# SCH_heterodyne.net
KiCad netlist of a schematic drawn in EasyEDA
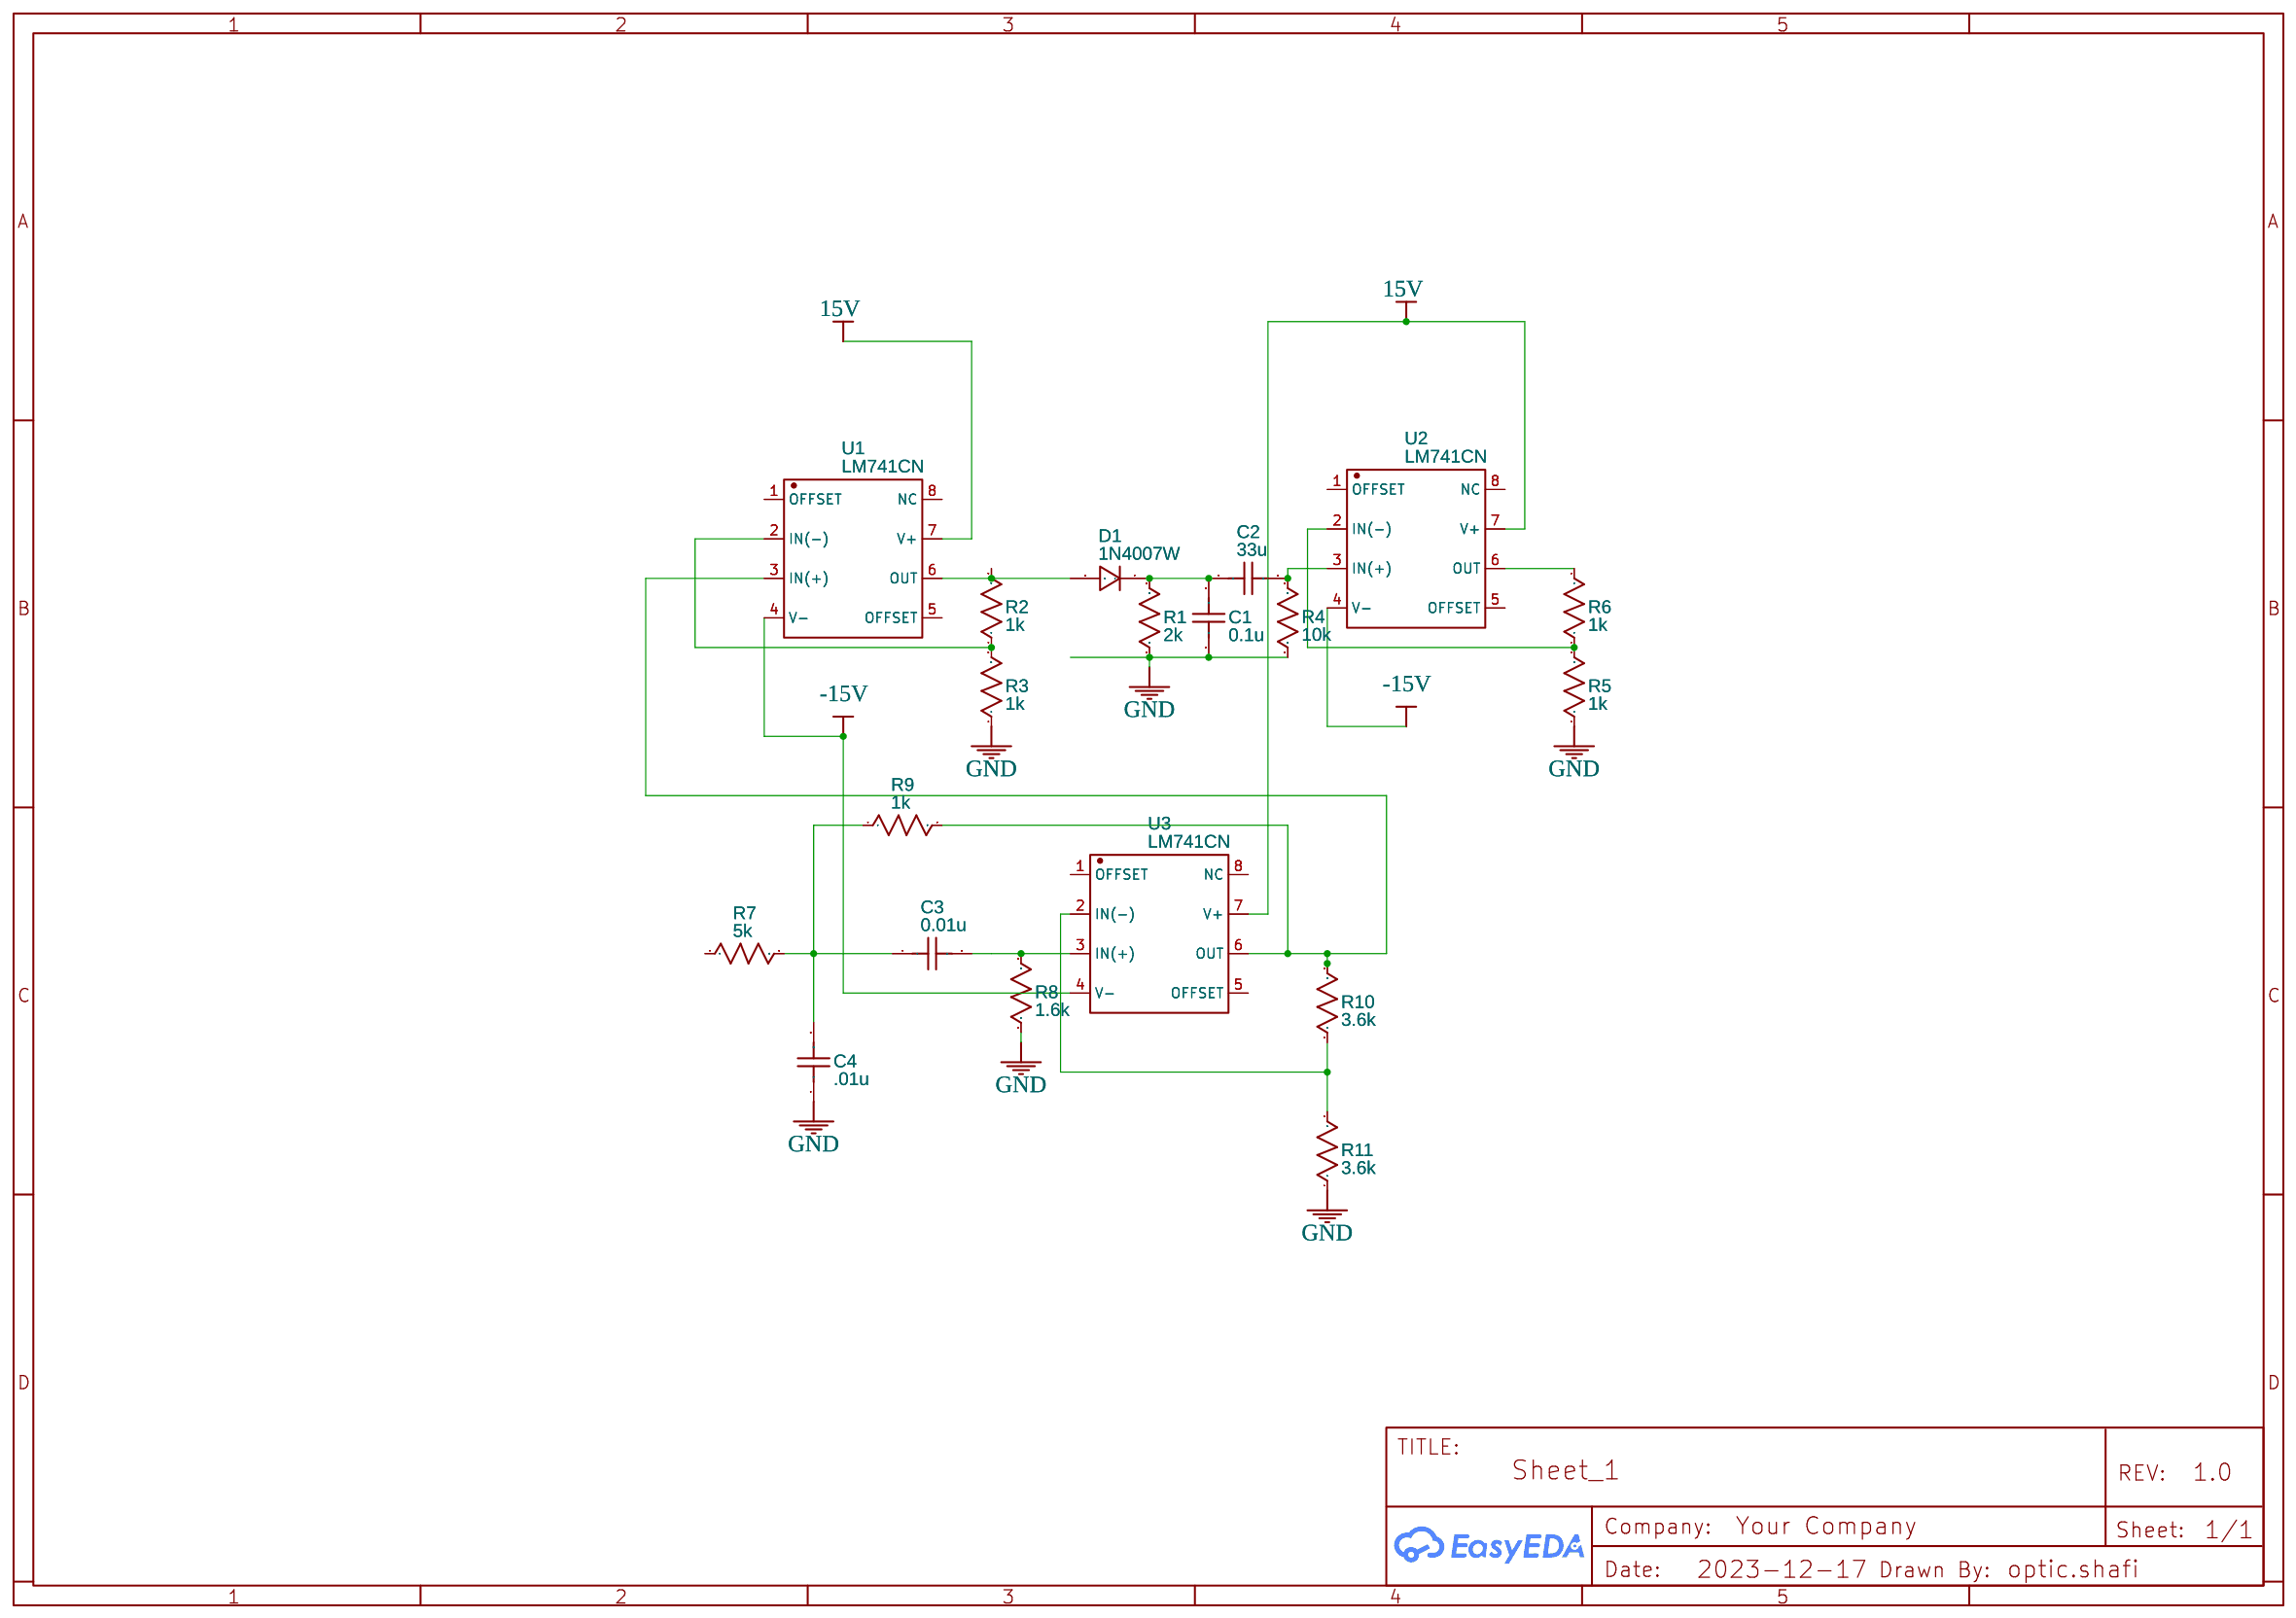
[diagram p0: schematic sheet]

(export (version "E")
  (design (tool "Eeschema 10.0.6"))
  (components
    (comp (ref "C1") (value "0.1u") (libsource (lib "") (part "C_0603_US_1")))
    (comp (ref "C2") (value "33u") (libsource (lib "") (part "C_0603_US")))
    (comp (ref "C3") (value "0.01u") (libsource (lib "") (part "C_0603_US")))
    (comp (ref "C4") (value ".01u") (libsource (lib "") (part "C_0603_US_1")))
    (comp (ref "D1")
      (value "1N4007W")
      (fields (field (name "Manufacturer") "BLUE ROCKET"))
      (libsource (lib "") (part "1N4007W"))
    )
    (comp (ref "R1") (value "2k") (libsource (lib "") (part "R_0603_US")))
    (comp (ref "R2") (value "1k") (libsource (lib "") (part "R_0603_US")))
    (comp (ref "R3") (value "1k") (libsource (lib "") (part "R_0603_US")))
    (comp (ref "R4") (value "10k") (libsource (lib "") (part "R_0603_US")))
    (comp (ref "R5") (value "1k") (libsource (lib "") (part "R_0603_US")))
    (comp (ref "R6") (value "1k") (libsource (lib "") (part "R_0603_US")))
    (comp (ref "R7") (value "5k") (libsource (lib "") (part "R_0603_US_1")))
    (comp (ref "R8") (value "1.6k") (libsource (lib "") (part "R_0603_US")))
    (comp (ref "R9") (value "1k") (libsource (lib "") (part "R_0603_US_1")))
    (comp (ref "R10") (value "3.6k") (libsource (lib "") (part "R_0603_US")))
    (comp (ref "R11") (value "3.6k") (libsource (lib "") (part "R_0603_US")))
    (comp (ref "U1")
      (value "LM741CN")
      (fields (field (name "Manufacturer Part") "LM741CN/NOPB") (field (name "Manufacturer") "TI(德州仪器)"))
      (libsource (lib "") (part "LM741CN"))
    )
    (comp (ref "U2")
      (value "LM741CN")
      (fields (field (name "Manufacturer Part") "LM741CN/NOPB") (field (name "Manufacturer") "TI(德州仪器)"))
      (libsource (lib "") (part "LM741CN"))
    )
    (comp (ref "U3")
      (value "LM741CN")
      (fields (field (name "Manufacturer Part") "LM741CN/NOPB") (field (name "Manufacturer") "TI(德州仪器)"))
      (libsource (lib "") (part "LM741CN"))
    )
  )
  (nets
    (net (code "1") (name "-15V") (class "Default")
      (node (ref "U1") (pin "4") (pinfunction "V-_4") (pintype "unspecified"))
      (node (ref "U2") (pin "4") (pinfunction "V-_4") (pintype "unspecified"))
      (node (ref "U3") (pin "4") (pinfunction "V-_4") (pintype "unspecified"))
    )
    (net (code "2") (name "15V") (class "Default")
      (node (ref "U1") (pin "7") (pinfunction "V+_7") (pintype "unspecified"))
      (node (ref "U2") (pin "7") (pinfunction "V+_7") (pintype "unspecified"))
      (node (ref "U3") (pin "7") (pinfunction "V+_7") (pintype "unspecified"))
    )
    (net (code "3") (name "GND") (class "Default")
      (node (ref "C1") (pin "1") (pinfunction "1_1") (pintype "unspecified"))
      (node (ref "C4") (pin "1") (pinfunction "1_1") (pintype "unspecified"))
      (node (ref "R1") (pin "1") (pinfunction "1_1") (pintype "unspecified"))
      (node (ref "R11") (pin "1") (pinfunction "1_1") (pintype "unspecified"))
      (node (ref "R3") (pin "1") (pinfunction "1_1") (pintype "unspecified"))
      (node (ref "R4") (pin "1") (pinfunction "1_1") (pintype "unspecified"))
      (node (ref "R5") (pin "1") (pinfunction "1_1") (pintype "unspecified"))
      (node (ref "R8") (pin "1") (pinfunction "1_1") (pintype "unspecified"))
    )
    (net (code "4") (name "Net-(C1-Pad2)") (class "Default")
      (node (ref "C1") (pin "2") (pinfunction "2_2") (pintype "unspecified"))
      (node (ref "C2") (pin "1") (pinfunction "1_1") (pintype "unspecified"))
      (node (ref "D1") (pin "1") (pinfunction "1_1") (pintype "unspecified"))
      (node (ref "R1") (pin "2") (pinfunction "2_2") (pintype "unspecified"))
    )
    (net (code "5") (name "Net-(C3-Pad1)") (class "Default")
      (node (ref "C3") (pin "1") (pinfunction "1_1") (pintype "unspecified"))
      (node (ref "C4") (pin "2") (pinfunction "2_2") (pintype "unspecified"))
      (node (ref "R7") (pin "2") (pinfunction "2_2") (pintype "unspecified"))
      (node (ref "R9") (pin "1") (pinfunction "1_1") (pintype "unspecified"))
    )
    (net (code "6") (name "Net-(U1-IN(+))") (class "Default")
      (node (ref "R10") (pin "2") (pinfunction "2_2") (pintype "unspecified"))
      (node (ref "R9") (pin "2") (pinfunction "2_2") (pintype "unspecified"))
      (node (ref "U1") (pin "3") (pinfunction "IN(+)_3") (pintype "unspecified"))
      (node (ref "U3") (pin "6") (pinfunction "OUT_6") (pintype "unspecified"))
    )
    (net (code "7") (name "Net-(U1-IN(-))") (class "Default")
      (node (ref "R2") (pin "1") (pinfunction "1_1") (pintype "unspecified"))
      (node (ref "R3") (pin "2") (pinfunction "2_2") (pintype "unspecified"))
      (node (ref "U1") (pin "2") (pinfunction "IN(-)_2") (pintype "unspecified"))
    )
    (net (code "8") (name "Net-(U1-OUT)") (class "Default")
      (node (ref "D1") (pin "2") (pinfunction "2_2") (pintype "unspecified"))
      (node (ref "R2") (pin "2") (pinfunction "2_2") (pintype "unspecified"))
      (node (ref "U1") (pin "6") (pinfunction "OUT_6") (pintype "unspecified"))
    )
    (net (code "9") (name "Net-(U2-IN(+))") (class "Default")
      (node (ref "C2") (pin "2") (pinfunction "2_2") (pintype "unspecified"))
      (node (ref "R4") (pin "2") (pinfunction "2_2") (pintype "unspecified"))
      (node (ref "U2") (pin "3") (pinfunction "IN(+)_3") (pintype "unspecified"))
    )
    (net (code "10") (name "Net-(U2-IN(-))") (class "Default")
      (node (ref "R5") (pin "2") (pinfunction "2_2") (pintype "unspecified"))
      (node (ref "R6") (pin "1") (pinfunction "1_1") (pintype "unspecified"))
      (node (ref "U2") (pin "2") (pinfunction "IN(-)_2") (pintype "unspecified"))
    )
    (net (code "11") (name "Net-(U2-OUT)") (class "Default")
      (node (ref "R6") (pin "2") (pinfunction "2_2") (pintype "unspecified"))
      (node (ref "U2") (pin "6") (pinfunction "OUT_6") (pintype "unspecified"))
    )
    (net (code "12") (name "Net-(U3-IN(+))") (class "Default")
      (node (ref "C3") (pin "2") (pinfunction "2_2") (pintype "unspecified"))
      (node (ref "R8") (pin "2") (pinfunction "2_2") (pintype "unspecified"))
      (node (ref "U3") (pin "3") (pinfunction "IN(+)_3") (pintype "unspecified"))
    )
    (net (code "13") (name "Net-(U3-IN(-))") (class "Default")
      (node (ref "R10") (pin "1") (pinfunction "1_1") (pintype "unspecified"))
      (node (ref "R11") (pin "2") (pinfunction "2_2") (pintype "unspecified"))
      (node (ref "U3") (pin "2") (pinfunction "IN(-)_2") (pintype "unspecified"))
    )
    (net (code "14") (name "unconnected-(R7-Pad1)") (class "Default")
      (node (ref "R7") (pin "1") (pinfunction "1_1") (pintype "unspecified"))
    )
    (net (code "15") (name "unconnected-(U1-NC-Pad8)") (class "Default")
      (node (ref "U1") (pin "8") (pinfunction "NC_8") (pintype "unspecified"))
    )
    (net (code "16") (name "unconnected-(U1-OFFSET-Pad1)") (class "Default")
      (node (ref "U1") (pin "1") (pinfunction "OFFSET_1") (pintype "unspecified"))
    )
    (net (code "17") (name "unconnected-(U1-OFFSET-Pad5)") (class "Default")
      (node (ref "U1") (pin "5") (pinfunction "OFFSET_5") (pintype "unspecified"))
    )
    (net (code "18") (name "unconnected-(U2-NC-Pad8)") (class "Default")
      (node (ref "U2") (pin "8") (pinfunction "NC_8") (pintype "unspecified"))
    )
    (net (code "19") (name "unconnected-(U2-OFFSET-Pad1)") (class "Default")
      (node (ref "U2") (pin "1") (pinfunction "OFFSET_1") (pintype "unspecified"))
    )
    (net (code "20") (name "unconnected-(U2-OFFSET-Pad5)") (class "Default")
      (node (ref "U2") (pin "5") (pinfunction "OFFSET_5") (pintype "unspecified"))
    )
    (net (code "21") (name "unconnected-(U3-NC-Pad8)") (class "Default")
      (node (ref "U3") (pin "8") (pinfunction "NC_8") (pintype "unspecified"))
    )
    (net (code "22") (name "unconnected-(U3-OFFSET-Pad1)") (class "Default")
      (node (ref "U3") (pin "1") (pinfunction "OFFSET_1") (pintype "unspecified"))
    )
    (net (code "23") (name "unconnected-(U3-OFFSET-Pad5)") (class "Default")
      (node (ref "U3") (pin "5") (pinfunction "OFFSET_5") (pintype "unspecified"))
    )
  )
)
